# ODR_override_rev_E.net
KiCad netlist of a schematic drawn in EAGLE
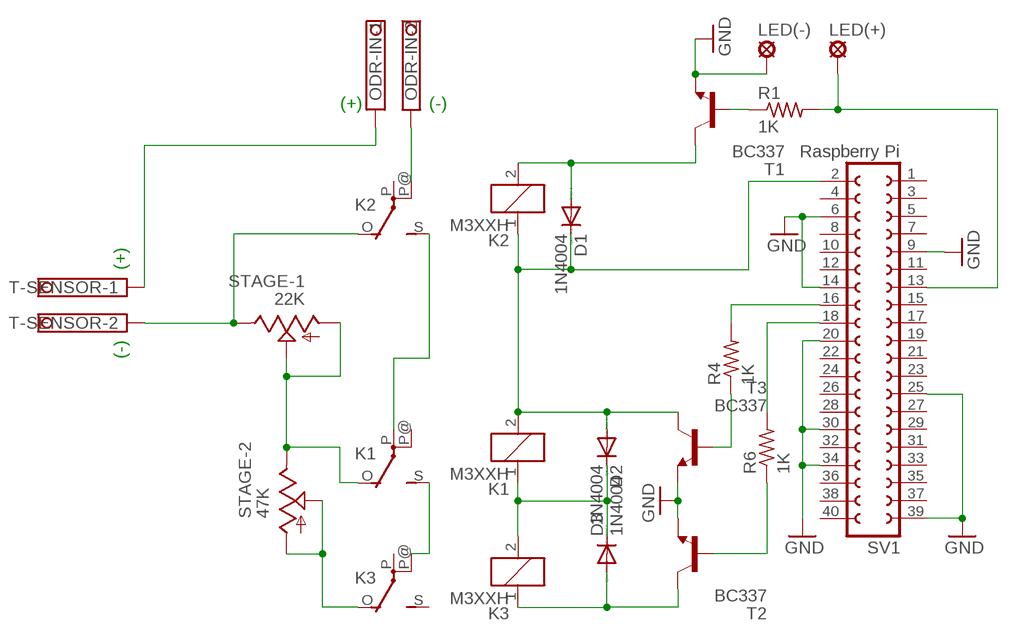
[diagram p0: schematic, sheet 1]

(export (version "E")
  (design (tool "Eeschema 10.0.6"))
  (components
    (comp (ref "D1")
      (value "1N4004")
      (footprint "eagle-import:DO41-10")
      (libsource (lib "eagle-import") (part "1N4004"))
    )
    (comp (ref "D2")
      (value "1N4004")
      (footprint "eagle-import:DO41-10")
      (libsource (lib "eagle-import") (part "1N4004"))
    )
    (comp (ref "D3")
      (value "1N4004")
      (footprint "eagle-import:DO41-10")
      (libsource (lib "eagle-import") (part "1N4004"))
    )
    (comp (ref "K1")
      (value "M3XXH")
      (footprint "eagle-import:M3XXH")
      (libsource (lib "eagle-import") (part "M3XXH"))
    )
    (comp (ref "K2")
      (value "M3XXH")
      (footprint "eagle-import:M3XXH")
      (libsource (lib "eagle-import") (part "M3XXH"))
    )
    (comp (ref "K3")
      (value "M3XXH")
      (footprint "eagle-import:M3XXH")
      (libsource (lib "eagle-import") (part "M3XXH"))
    )
    (comp (ref "LED(+)")
      (value "LSP11")
      (footprint "eagle-import:LSP11")
      (libsource (lib "eagle-import") (part "LSP11"))
    )
    (comp (ref "LED(-)")
      (value "LSP11")
      (footprint "eagle-import:LSP11")
      (libsource (lib "eagle-import") (part "LSP11"))
    )
    (comp (ref "ODR-IN")
      (value "TERMINAL-BLOCK-3.5MM-2-PIN-ROUND-PAD")
      (footprint "eagle-import:TERMINAL-BLOCK-2-PIN-3.5MM-ROUND-PAD")
      (libsource (lib "eagle-import") (part "TERMINAL-BLOCK-3.5MM-2-PIN-ROUND-PAD"))
    )
    (comp (ref "R1")
      (value "1K")
      (footprint "eagle-import:0204_5")
      (libsource (lib "eagle-import") (part "R-US_0204/5"))
    )
    (comp (ref "R4")
      (value "1K")
      (footprint "eagle-import:0204_5")
      (libsource (lib "eagle-import") (part "R-US_0204/5"))
    )
    (comp (ref "R6")
      (value "1K")
      (footprint "eagle-import:0204_5")
      (libsource (lib "eagle-import") (part "R-US_0204/5"))
    )
    (comp (ref "STAGE-1")
      (value "22K")
      (footprint "eagle-import:B25P")
      (libsource (lib "eagle-import") (part "TRIM_US-B25P"))
    )
    (comp (ref "STAGE-2")
      (value "47K")
      (footprint "eagle-import:B25P")
      (libsource (lib "eagle-import") (part "TRIM_US-B25P"))
    )
    (comp (ref "SV1")
      (value "Raspberry Pi")
      (footprint "eagle-import:FE20-2")
      (libsource (lib "eagle-import") (part "FE20-2"))
    )
    (comp (ref "T-SENSOR")
      (value "TERMINAL-BLOCK-3.5MM-2-PIN-ROUND-PAD")
      (footprint "eagle-import:TERMINAL-BLOCK-2-PIN-3.5MM-ROUND-PAD")
      (libsource (lib "eagle-import") (part "TERMINAL-BLOCK-3.5MM-2-PIN-ROUND-PAD"))
    )
    (comp (ref "T1")
      (value "BC337")
      (footprint "eagle-import:TO92")
      (libsource (lib "eagle-import") (part "BC337"))
    )
    (comp (ref "T2")
      (value "BC337")
      (footprint "eagle-import:TO92")
      (libsource (lib "eagle-import") (part "BC337"))
    )
    (comp (ref "T3")
      (value "BC337")
      (footprint "eagle-import:TO92")
      (libsource (lib "eagle-import") (part "BC337"))
    )
  )
  (nets
    (net (code "1") (name "GND") (class "Default")
      (node (ref "LED(-)") (pin "MP") (pinfunction "MP_MP") (pintype "passive"))
      (node (ref "SV1") (pin "14") (pinfunction "14_14") (pintype "passive"))
      (node (ref "SV1") (pin "20") (pinfunction "20_20") (pintype "passive"))
      (node (ref "SV1") (pin "25") (pinfunction "25_25") (pintype "passive"))
      (node (ref "SV1") (pin "30") (pinfunction "30_30") (pintype "passive"))
      (node (ref "SV1") (pin "34") (pinfunction "34_34") (pintype "passive"))
      (node (ref "SV1") (pin "39") (pinfunction "39_39") (pintype "passive"))
      (node (ref "SV1") (pin "6") (pinfunction "6_6") (pintype "passive"))
      (node (ref "SV1") (pin "9") (pinfunction "9_9") (pintype "passive"))
      (node (ref "T1") (pin "1") (pinfunction "E_1") (pintype "passive"))
      (node (ref "T2") (pin "1") (pinfunction "E_1") (pintype "passive"))
      (node (ref "T3") (pin "1") (pinfunction "E_1") (pintype "passive"))
    )
    (net (code "2") (name "Net-(D2-PadC)") (class "Default")
      (node (ref "D2") (pin "C") (pinfunction "C_C") (pintype "passive"))
      (node (ref "D3") (pin "C") (pinfunction "C_C") (pintype "passive"))
      (node (ref "K1") (pin "1") (pinfunction "1_1") (pintype "passive"))
      (node (ref "K3") (pin "2") (pinfunction "2_2") (pintype "passive"))
    )
    (net (code "3") (name "Net-(K1-PadO)") (class "Default")
      (node (ref "K1") (pin "O") (pinfunction "O_O") (pintype "passive"))
      (node (ref "STAGE-1") (pin "A") (pinfunction "A_A") (pintype "passive"))
      (node (ref "STAGE-1") (pin "S") (pinfunction "S_S") (pintype "passive"))
      (node (ref "STAGE-2") (pin "E") (pinfunction "E_E") (pintype "passive"))
    )
    (net (code "4") (name "Net-(K1-PadP)") (class "Default")
      (node (ref "K1") (pin "P") (pinfunction "P_P") (pintype "passive"))
      (node (ref "K2") (pin "S") (pinfunction "S_S") (pintype "passive"))
    )
    (net (code "5") (name "Net-(K1-PadS)") (class "Default")
      (node (ref "K1") (pin "S") (pinfunction "S_S") (pintype "passive"))
      (node (ref "K3") (pin "P@") (pinfunction "P_P@") (pintype "passive"))
    )
    (net (code "6") (name "Net-(K3-PadO)") (class "Default")
      (node (ref "K3") (pin "O") (pinfunction "O_O") (pintype "passive"))
      (node (ref "STAGE-2") (pin "A") (pinfunction "A_A") (pintype "passive"))
      (node (ref "STAGE-2") (pin "S") (pinfunction "S_S") (pintype "passive"))
    )
    (net (code "7") (name "Net-(LED(+)-PadMP)") (class "Default")
      (node (ref "LED(+)") (pin "MP") (pinfunction "MP_MP") (pintype "passive"))
      (node (ref "R1") (pin "2") (pinfunction "2_2") (pintype "passive"))
      (node (ref "SV1") (pin "13") (pinfunction "13_13") (pintype "passive"))
    )
    (net (code "8") (name "Net-(ODR-INA-K)") (class "Default")
      (node (ref "ODR-IN") (pin "1") (pinfunction "K_1") (pintype "passive"))
      (node (ref "T-SENSOR") (pin "1") (pinfunction "K_1") (pintype "passive"))
    )
    (net (code "9") (name "Net-(ODR-INB-K)") (class "Default")
      (node (ref "K2") (pin "P@") (pinfunction "P_P@") (pintype "passive"))
      (node (ref "ODR-IN") (pin "2") (pinfunction "K_2") (pintype "passive"))
    )
    (net (code "10") (name "Net-(R4-Pad2)") (class "Default")
      (node (ref "R4") (pin "2") (pinfunction "2_2") (pintype "passive"))
      (node (ref "SV1") (pin "16") (pinfunction "16_16") (pintype "passive"))
    )
    (net (code "11") (name "Net-(R6-Pad2)") (class "Default")
      (node (ref "R6") (pin "2") (pinfunction "2_2") (pintype "passive"))
      (node (ref "SV1") (pin "18") (pinfunction "18_18") (pintype "passive"))
    )
    (net (code "12") (name "Net-(T-SENSORB-K)") (class "Default")
      (node (ref "K2") (pin "O") (pinfunction "O_O") (pintype "passive"))
      (node (ref "STAGE-1") (pin "E") (pinfunction "E_E") (pintype "passive"))
      (node (ref "T-SENSOR") (pin "2") (pinfunction "K_2") (pintype "passive"))
    )
    (net (code "13") (name "Net-(T1-B)") (class "Default")
      (node (ref "R1") (pin "1") (pinfunction "1_1") (pintype "passive"))
      (node (ref "T1") (pin "2") (pinfunction "B_2") (pintype "passive"))
    )
    (net (code "14") (name "Net-(T1-C)") (class "Default")
      (node (ref "D1") (pin "A") (pinfunction "A_A") (pintype "passive"))
      (node (ref "K2") (pin "2") (pinfunction "2_2") (pintype "passive"))
      (node (ref "T1") (pin "3") (pinfunction "C_3") (pintype "passive"))
    )
    (net (code "15") (name "Net-(T2-B)") (class "Default")
      (node (ref "R6") (pin "1") (pinfunction "1_1") (pintype "passive"))
      (node (ref "T2") (pin "2") (pinfunction "B_2") (pintype "passive"))
    )
    (net (code "16") (name "Net-(T2-C)") (class "Default")
      (node (ref "D3") (pin "A") (pinfunction "A_A") (pintype "passive"))
      (node (ref "K3") (pin "1") (pinfunction "1_1") (pintype "passive"))
      (node (ref "T2") (pin "3") (pinfunction "C_3") (pintype "passive"))
    )
    (net (code "17") (name "Net-(T3-B)") (class "Default")
      (node (ref "R4") (pin "1") (pinfunction "1_1") (pintype "passive"))
      (node (ref "T3") (pin "2") (pinfunction "B_2") (pintype "passive"))
    )
    (net (code "18") (name "Net-(T3-C)") (class "Default")
      (node (ref "D1") (pin "C") (pinfunction "C_C") (pintype "passive"))
      (node (ref "D2") (pin "A") (pinfunction "A_A") (pintype "passive"))
      (node (ref "K1") (pin "2") (pinfunction "2_2") (pintype "passive"))
      (node (ref "K2") (pin "1") (pinfunction "1_1") (pintype "passive"))
      (node (ref "SV1") (pin "2") (pinfunction "2_2") (pintype "passive"))
      (node (ref "T3") (pin "3") (pinfunction "C_3") (pintype "passive"))
    )
    (net (code "19") (name "unconnected-(K1B-P-PadP@)") (class "Default")
      (node (ref "K1") (pin "P@") (pinfunction "P_P@") (pintype "passive"))
    )
    (net (code "20") (name "unconnected-(K2-PadP)") (class "Default")
      (node (ref "K2") (pin "P") (pinfunction "P_P") (pintype "passive"))
    )
    (net (code "21") (name "unconnected-(K3-PadP)") (class "Default")
      (node (ref "K3") (pin "P") (pinfunction "P_P") (pintype "passive"))
    )
    (net (code "22") (name "unconnected-(K3-PadS)") (class "Default")
      (node (ref "K3") (pin "S") (pinfunction "S_S") (pintype "passive"))
    )
    (net (code "23") (name "unconnected-(SV1-Pad1)") (class "Default")
      (node (ref "SV1") (pin "1") (pinfunction "1_1") (pintype "passive"))
    )
    (net (code "24") (name "unconnected-(SV1-Pad3)") (class "Default")
      (node (ref "SV1") (pin "3") (pinfunction "3_3") (pintype "passive"))
    )
    (net (code "25") (name "unconnected-(SV1-Pad4)") (class "Default")
      (node (ref "SV1") (pin "4") (pinfunction "4_4") (pintype "passive"))
    )
    (net (code "26") (name "unconnected-(SV1-Pad5)") (class "Default")
      (node (ref "SV1") (pin "5") (pinfunction "5_5") (pintype "passive"))
    )
    (net (code "27") (name "unconnected-(SV1-Pad7)") (class "Default")
      (node (ref "SV1") (pin "7") (pinfunction "7_7") (pintype "passive"))
    )
    (net (code "28") (name "unconnected-(SV1-Pad8)") (class "Default")
      (node (ref "SV1") (pin "8") (pinfunction "8_8") (pintype "passive"))
    )
    (net (code "29") (name "unconnected-(SV1-Pad10)") (class "Default")
      (node (ref "SV1") (pin "10") (pinfunction "10_10") (pintype "passive"))
    )
    (net (code "30") (name "unconnected-(SV1-Pad11)") (class "Default")
      (node (ref "SV1") (pin "11") (pinfunction "11_11") (pintype "passive"))
    )
    (net (code "31") (name "unconnected-(SV1-Pad12)") (class "Default")
      (node (ref "SV1") (pin "12") (pinfunction "12_12") (pintype "passive"))
    )
    (net (code "32") (name "unconnected-(SV1-Pad15)") (class "Default")
      (node (ref "SV1") (pin "15") (pinfunction "15_15") (pintype "passive"))
    )
    (net (code "33") (name "unconnected-(SV1-Pad17)") (class "Default")
      (node (ref "SV1") (pin "17") (pinfunction "17_17") (pintype "passive"))
    )
    (net (code "34") (name "unconnected-(SV1-Pad19)") (class "Default")
      (node (ref "SV1") (pin "19") (pinfunction "19_19") (pintype "passive"))
    )
    (net (code "35") (name "unconnected-(SV1-Pad21)") (class "Default")
      (node (ref "SV1") (pin "21") (pinfunction "21_21") (pintype "passive"))
    )
    (net (code "36") (name "unconnected-(SV1-Pad22)") (class "Default")
      (node (ref "SV1") (pin "22") (pinfunction "22_22") (pintype "passive"))
    )
    (net (code "37") (name "unconnected-(SV1-Pad23)") (class "Default")
      (node (ref "SV1") (pin "23") (pinfunction "23_23") (pintype "passive"))
    )
    (net (code "38") (name "unconnected-(SV1-Pad24)") (class "Default")
      (node (ref "SV1") (pin "24") (pinfunction "24_24") (pintype "passive"))
    )
    (net (code "39") (name "unconnected-(SV1-Pad26)") (class "Default")
      (node (ref "SV1") (pin "26") (pinfunction "26_26") (pintype "passive"))
    )
    (net (code "40") (name "unconnected-(SV1-Pad27)") (class "Default")
      (node (ref "SV1") (pin "27") (pinfunction "27_27") (pintype "passive"))
    )
    (net (code "41") (name "unconnected-(SV1-Pad28)") (class "Default")
      (node (ref "SV1") (pin "28") (pinfunction "28_28") (pintype "passive"))
    )
    (net (code "42") (name "unconnected-(SV1-Pad29)") (class "Default")
      (node (ref "SV1") (pin "29") (pinfunction "29_29") (pintype "passive"))
    )
    (net (code "43") (name "unconnected-(SV1-Pad31)") (class "Default")
      (node (ref "SV1") (pin "31") (pinfunction "31_31") (pintype "passive"))
    )
    (net (code "44") (name "unconnected-(SV1-Pad32)") (class "Default")
      (node (ref "SV1") (pin "32") (pinfunction "32_32") (pintype "passive"))
    )
    (net (code "45") (name "unconnected-(SV1-Pad33)") (class "Default")
      (node (ref "SV1") (pin "33") (pinfunction "33_33") (pintype "passive"))
    )
    (net (code "46") (name "unconnected-(SV1-Pad35)") (class "Default")
      (node (ref "SV1") (pin "35") (pinfunction "35_35") (pintype "passive"))
    )
    (net (code "47") (name "unconnected-(SV1-Pad36)") (class "Default")
      (node (ref "SV1") (pin "36") (pinfunction "36_36") (pintype "passive"))
    )
    (net (code "48") (name "unconnected-(SV1-Pad37)") (class "Default")
      (node (ref "SV1") (pin "37") (pinfunction "37_37") (pintype "passive"))
    )
    (net (code "49") (name "unconnected-(SV1-Pad38)") (class "Default")
      (node (ref "SV1") (pin "38") (pinfunction "38_38") (pintype "passive"))
    )
    (net (code "50") (name "unconnected-(SV1-Pad40)") (class "Default")
      (node (ref "SV1") (pin "40") (pinfunction "40_40") (pintype "passive"))
    )
  )
)
